# kr2_2.net
KiCad netlist of a schematic drawn in Altium Designer
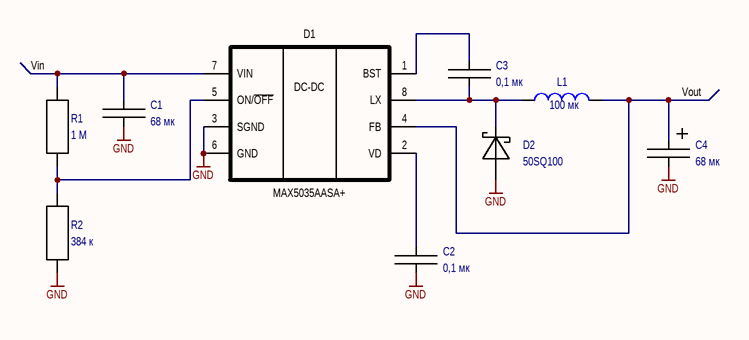
[diagram p0: kr2_2.SchDoc]

(export (version "E")
  (design (tool "Eeschema 10.0.6"))
  (components
    (comp (ref "C1")
      (value "68 мк")
      (fields (field (name "Comment") "68 мкФ ±* * * *, *"))
      (libsource (lib "STO") (part "C"))
    )
    (comp (ref "C2")
      (value "0,1 мк")
      (fields (field (name "Comment") "0,1 мкФ ±* * * *, *"))
      (libsource (lib "STO") (part "C"))
    )
    (comp (ref "C3")
      (value "0,1 мк")
      (fields (field (name "Comment") "0,1 мкФ ±* * * *, *"))
      (libsource (lib "STO") (part "C"))
    )
    (comp (ref "C4")
      (value "68 мк")
      (fields (field (name "Comment") "68 мкФ ±* * * *, *"))
      (libsource (lib "STO") (part "C+"))
    )
    (comp (ref "D1") (value "MAX5035AASA+") (libsource (lib "STO") (part "MAX5035AASA+")))
    (comp (ref "D2") (value "50SQ100") (libsource (lib "STO") (part "50SQ100")))
    (comp (ref "L1")
      (value "100 мк")
      (description "Inductor")
      (libsource (lib "Simulation Generic Components") (part "Inductor"))
    )
    (comp (ref "R1")
      (value "1 М")
      (fields (field (name "Comment") "1 МОм ±* *, *"))
      (libsource (lib "STO") (part "R"))
    )
    (comp (ref "R2")
      (value "384 к")
      (fields (field (name "Comment") "384 кОм ±* *, *"))
      (libsource (lib "STO") (part "R"))
    )
  )
  (nets
    (net (code "1") (name "/Vin") (class "Default")
      (node (ref "C1") (pin "2") (pinfunction "2_2") (pintype "passive"))
      (node (ref "D1") (pin "7") (pinfunction "VIN_7") (pintype "passive"))
      (node (ref "R1") (pin "1") (pinfunction "1_1") (pintype "passive"))
    )
    (net (code "2") (name "/Vout") (class "Default")
      (node (ref "C4") (pin "1") (pinfunction "1_1") (pintype "passive"))
      (node (ref "D1") (pin "4") (pinfunction "FB_4") (pintype "passive"))
      (node (ref "L1") (pin "2") (pinfunction "2_2") (pintype "passive"))
    )
    (net (code "3") (name "GND") (class "Default")
      (node (ref "C1") (pin "1") (pinfunction "1_1") (pintype "passive"))
      (node (ref "C2") (pin "1") (pinfunction "1_1") (pintype "passive"))
      (node (ref "C4") (pin "2") (pinfunction "2_2") (pintype "passive"))
      (node (ref "D1") (pin "3") (pinfunction "SGND_3") (pintype "passive"))
      (node (ref "D1") (pin "6") (pinfunction "GND_6") (pintype "passive"))
      (node (ref "D2") (pin "1") (pinfunction "A_1") (pintype "passive"))
      (node (ref "R2") (pin "2") (pinfunction "2_2") (pintype "passive"))
    )
    (net (code "4") (name "Net-(D1-BST)") (class "Default")
      (node (ref "C3") (pin "2") (pinfunction "2_2") (pintype "passive"))
      (node (ref "D1") (pin "1") (pinfunction "BST_1") (pintype "passive"))
    )
    (net (code "5") (name "Net-(D1-LX)") (class "Default")
      (node (ref "C3") (pin "1") (pinfunction "1_1") (pintype "passive"))
      (node (ref "D1") (pin "8") (pinfunction "LX_8") (pintype "passive"))
      (node (ref "D2") (pin "1") (pinfunction "C_1") (pintype "passive"))
      (node (ref "L1") (pin "1") (pinfunction "1_1") (pintype "passive"))
    )
    (net (code "6") (name "Net-(D1-ON{slash}~{OFF})") (class "Default")
      (node (ref "D1") (pin "5") (pinfunction "ON/~{OFF}_5") (pintype "passive"))
      (node (ref "R1") (pin "2") (pinfunction "2_2") (pintype "passive"))
      (node (ref "R2") (pin "1") (pinfunction "1_1") (pintype "passive"))
    )
    (net (code "7") (name "Net-(D1-VD)") (class "Default")
      (node (ref "C2") (pin "2") (pinfunction "2_2") (pintype "passive"))
      (node (ref "D1") (pin "2") (pinfunction "VD_2") (pintype "passive"))
    )
  )
)
